# relais_platine_v6.net
KiCad netlist of a schematic drawn in EAGLE
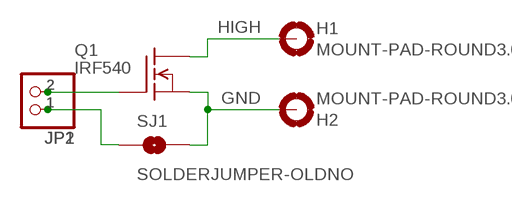
[diagram p0: schematic, sheet 1]

(export (version "E")
  (design (tool "Eeschema 10.0.6"))
  (components
    (comp (ref "H1")
      (value "MOUNT-PAD-ROUND3.0")
      (footprint "eagle-import:3,0-PAD")
      (libsource (lib "eagle-import") (part "MOUNT-PAD-ROUND3.0"))
    )
    (comp (ref "H2")
      (value "MOUNT-PAD-ROUND3.0")
      (footprint "eagle-import:3,0-PAD")
      (libsource (lib "eagle-import") (part "MOUNT-PAD-ROUND3.0"))
    )
    (comp (ref "JP1")
      (value "PINHD-1X2")
      (footprint "eagle-import:1X02")
      (libsource (lib "eagle-import") (part "PINHD-1X2"))
    )
    (comp (ref "JP2")
      (value "PINHD-1X2/90")
      (footprint "eagle-import:1X02_90")
      (libsource (lib "eagle-import") (part "PINHD-1X2/90"))
    )
    (comp (ref "Q1")
      (value "IRF540")
      (footprint "eagle-import:TO220")
      (libsource (lib "eagle-import") (part "IRF540"))
    )
    (comp (ref "SJ1")
      (value "SOLDERJUMPER-OLDNO")
      (footprint "eagle-import:SJ_2S-NO")
      (libsource (lib "eagle-import") (part "SOLDERJUMPER-OLDNO"))
    )
  )
  (nets
    (net (code "1") (name "/GND") (class "Default")
      (node (ref "H2") (pin "B3,0") (pinfunction "MOUNT_B3,0") (pintype "passive"))
      (node (ref "Q1") (pin "3") (pinfunction "S_3") (pintype "passive"))
      (node (ref "SJ1") (pin "2") (pinfunction "2_2") (pintype "passive"))
    )
    (net (code "2") (name "/HIGH") (class "Default")
      (node (ref "H1") (pin "B3,0") (pinfunction "MOUNT_B3,0") (pintype "passive"))
      (node (ref "Q1") (pin "2") (pinfunction "D_2") (pintype "passive"))
    )
    (net (code "3") (name "Net-(JP1-Pad1)") (class "Default")
      (node (ref "JP1") (pin "1") (pinfunction "1_1") (pintype "passive"))
      (node (ref "JP2") (pin "1") (pinfunction "1_1") (pintype "passive"))
      (node (ref "SJ1") (pin "1") (pinfunction "1_1") (pintype "passive"))
    )
    (net (code "4") (name "Net-(Q1-G)") (class "Default")
      (node (ref "JP1") (pin "2") (pinfunction "2_2") (pintype "passive"))
      (node (ref "JP2") (pin "2") (pinfunction "2_2") (pintype "passive"))
      (node (ref "Q1") (pin "1") (pinfunction "G_1") (pintype "passive"))
    )
  )
)
